# Audio.net
KiCad netlist of a schematic drawn in Altium Designer
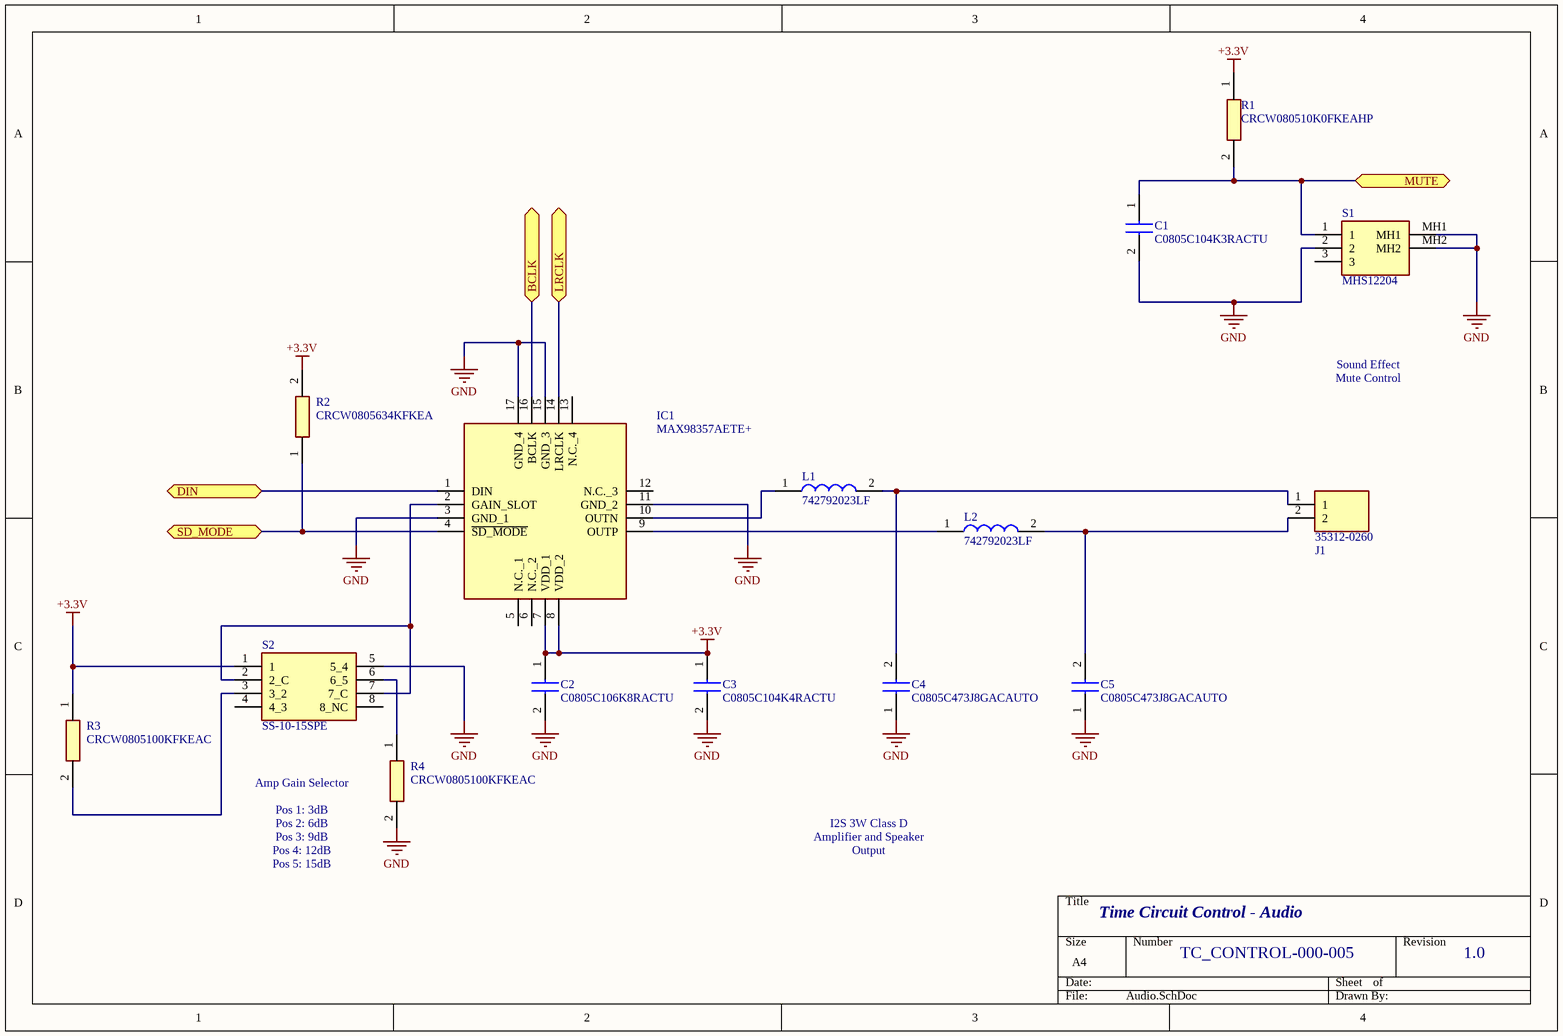
[diagram p0: Audio.SchDoc]

(export (version "E")
  (design (tool "Eeschema 10.0.6"))
  (components
    (comp (ref "C1")
      (value "C0805C104K3RACTU")
      (footprint "SamacSys:CAPC2012X88N")
      (description "Capacitor")
      (fields (field (name "MOUSER PART NUMBER") "80-C0805C104K3R"))
      (libsource (lib "SamacSys") (part "C0805C104K3RACTU"))
    )
    (comp (ref "C2")
      (value "C0805C106K8RACTU")
      (footprint "SamacSys:C0805")
      (description "Capacitor")
      (fields (field (name "MOUSER PART NUMBER") "80-C0805C106K8R"))
      (libsource (lib "SamacSys") (part "C0805C106K8RACTU"))
    )
    (comp (ref "C3")
      (value "C0805C104K4RACTU")
      (footprint "SamacSys:CAPC2012X88N")
      (description "Capacitor")
      (fields (field (name "MOUSER PART NUMBER") "80-C0805C104K4R"))
      (libsource (lib "SamacSys") (part "C0805C104K4RACTU"))
    )
    (comp (ref "C4")
      (value "C0805C473J8GACAUTO")
      (footprint "SamacSys:C0805")
      (description "Capacitor")
      (fields (field (name "MOUSER PART NUMBER") "80-C0805C473J8GAUTO"))
      (libsource (lib "SamacSys") (part "C0805C473J8GACAUTO"))
    )
    (comp (ref "C5")
      (value "C0805C473J8GACAUTO")
      (footprint "SamacSys:C0805")
      (description "Capacitor")
      (fields (field (name "MOUSER PART NUMBER") "80-C0805C473J8GAUTO"))
      (libsource (lib "SamacSys") (part "C0805C473J8GACAUTO"))
    )
    (comp (ref "IC1")
      (value "MAX98357AETE+")
      (footprint "SamacSys:QFN50P300X300X80-17N")
      (description "Integrated Circuit")
      (fields (field (name "MOUSER PART NUMBER") "700-MAX98357AETE+"))
      (libsource (lib "SamacSys") (part "MAX98357AETE+"))
    )
    (comp (ref "J1")
      (value "35312-0260")
      (footprint "SamacSys:SHDR2W64P0X250_1X2_746X650X700P")
      (description "Connector")
      (fields (field (name "MOUSER PART NUMBER") "538-35312-0260"))
      (libsource (lib "SamacSys") (part "35312-0260"))
    )
    (comp (ref "L1")
      (value "742792023LF")
      (footprint "SamacSys:CAPC2012X110N")
      (description "Inductor")
      (libsource (lib "SamacSys") (part "742792023LF"))
    )
    (comp (ref "L2")
      (value "742792023LF")
      (footprint "SamacSys:CAPC2012X110N")
      (description "Inductor")
      (libsource (lib "SamacSys") (part "742792023LF"))
    )
    (comp (ref "R1")
      (value "CRCW080510K0FKEAHP")
      (footprint "SamacSys:RESC2012X60N")
      (description "Resistor")
      (fields (field (name "MOUSER PART NUMBER") "71-CRCW080510K0FKEAH"))
      (libsource (lib "SamacSys") (part "CRCW080510K0FKEAHP"))
    )
    (comp (ref "R2")
      (value "CRCW0805634KFKEA")
      (footprint "SamacSys:RESC2012X50N")
      (description "Resistor")
      (fields (field (name "MOUSER PART NUMBER") "71-CRCW0805634KFKEA"))
      (libsource (lib "SamacSys") (part "CRCW0805634KFKEA"))
    )
    (comp (ref "R3")
      (value "CRCW0805100KFKEAC")
      (footprint "SamacSys:RESC2012X60N")
      (description "Resistor")
      (fields (field (name "MOUSER PART NUMBER") "71-CRCW0805100KFKEAC"))
      (libsource (lib "SamacSys") (part "CRCW0805100KFKEAC"))
    )
    (comp (ref "R4")
      (value "CRCW0805100KFKEAC")
      (footprint "SamacSys:RESC2012X60N")
      (description "Resistor")
      (fields (field (name "MOUSER PART NUMBER") "71-CRCW0805100KFKEAC"))
      (libsource (lib "SamacSys") (part "CRCW0805100KFKEAC"))
    )
    (comp (ref "S1")
      (value "MHS12204")
      (footprint "SamacSys:MHS12204")
      (description "Switch")
      (fields (field (name "MOUSER PART NUMBER") "506-MHS12204"))
      (libsource (lib "SamacSys") (part "MHS12204"))
    )
    (comp (ref "S2")
      (value "SS-10-15SPE")
      (footprint "SamacSys:SS1015SPE")
      (description "Switch")
      (libsource (lib "SamacSys") (part "SS-10-15SPE"))
    )
  )
  (nets
    (net (code "1") (name "+3.3V") (class "Default")
      (node (ref "C2") (pin "1") (pinfunction "1_1") (pintype "passive"))
      (node (ref "C3") (pin "1") (pinfunction "1_1") (pintype "passive"))
      (node (ref "IC1") (pin "7") (pinfunction "VDD_1_7") (pintype "passive"))
      (node (ref "IC1") (pin "8") (pinfunction "VDD_2_8") (pintype "passive"))
      (node (ref "R1") (pin "1") (pinfunction "1_1") (pintype "passive"))
      (node (ref "R2") (pin "2") (pinfunction "2_2") (pintype "passive"))
      (node (ref "R3") (pin "1") (pinfunction "1_1") (pintype "passive"))
      (node (ref "S2") (pin "1") (pinfunction "1_1") (pintype "passive"))
    )
    (net (code "2") (name "/BCLK") (class "Default")
      (node (ref "IC1") (pin "16") (pinfunction "BCLK_16") (pintype "passive"))
    )
    (net (code "3") (name "/DIN") (class "Default")
      (node (ref "IC1") (pin "1") (pinfunction "DIN_1") (pintype "passive"))
    )
    (net (code "4") (name "/LRCLK") (class "Default")
      (node (ref "IC1") (pin "14") (pinfunction "LRCLK_14") (pintype "passive"))
    )
    (net (code "5") (name "/MUTE") (class "Default")
      (node (ref "C1") (pin "1") (pinfunction "1_1") (pintype "passive"))
      (node (ref "R1") (pin "2") (pinfunction "2_2") (pintype "passive"))
      (node (ref "S1") (pin "1") (pinfunction "1_1") (pintype "passive"))
    )
    (net (code "6") (name "/SD_MODE") (class "Default")
      (node (ref "IC1") (pin "4") (pinfunction "~{SD_MODE}_4") (pintype "passive"))
      (node (ref "R2") (pin "1") (pinfunction "1_1") (pintype "passive"))
    )
    (net (code "7") (name "GND") (class "Default")
      (node (ref "C1") (pin "2") (pinfunction "2_2") (pintype "passive"))
      (node (ref "C2") (pin "2") (pinfunction "2_2") (pintype "passive"))
      (node (ref "C3") (pin "2") (pinfunction "2_2") (pintype "passive"))
      (node (ref "C4") (pin "1") (pinfunction "1_1") (pintype "passive"))
      (node (ref "C5") (pin "1") (pinfunction "1_1") (pintype "passive"))
      (node (ref "IC1") (pin "11") (pinfunction "GND_2_11") (pintype "passive"))
      (node (ref "IC1") (pin "15") (pinfunction "GND_3_15") (pintype "passive"))
      (node (ref "IC1") (pin "17") (pinfunction "GND_4_17") (pintype "passive"))
      (node (ref "IC1") (pin "3") (pinfunction "GND_1_3") (pintype "passive"))
      (node (ref "R4") (pin "2") (pinfunction "2_2") (pintype "passive"))
      (node (ref "S1") (pin "2") (pinfunction "2_2") (pintype "passive"))
      (node (ref "S1") (pin "MH1") (pinfunction "MH1_MH1") (pintype "passive"))
      (node (ref "S1") (pin "MH2") (pinfunction "MH2_MH2") (pintype "passive"))
      (node (ref "S2") (pin "5") (pinfunction "5_4_5") (pintype "passive"))
    )
    (net (code "8") (name "Net-(C4-Pad2)") (class "Default")
      (node (ref "C4") (pin "2") (pinfunction "2_2") (pintype "passive"))
      (node (ref "J1") (pin "1") (pinfunction "1_1") (pintype "passive"))
      (node (ref "L1") (pin "2") (pinfunction "2_2") (pintype "passive"))
    )
    (net (code "9") (name "Net-(C5-Pad2)") (class "Default")
      (node (ref "C5") (pin "2") (pinfunction "2_2") (pintype "passive"))
      (node (ref "J1") (pin "2") (pinfunction "2_2") (pintype "passive"))
      (node (ref "L2") (pin "2") (pinfunction "2_2") (pintype "passive"))
    )
    (net (code "10") (name "Net-(IC1-GAIN_SLOT)") (class "Default")
      (node (ref "IC1") (pin "2") (pinfunction "GAIN_SLOT_2") (pintype "passive"))
      (node (ref "S2") (pin "2") (pinfunction "2_C_2") (pintype "passive"))
      (node (ref "S2") (pin "7") (pinfunction "7_C_7") (pintype "passive"))
    )
    (net (code "11") (name "Net-(IC1-OUTN)") (class "Default")
      (node (ref "IC1") (pin "10") (pinfunction "OUTN_10") (pintype "passive"))
      (node (ref "L1") (pin "1") (pinfunction "1_1") (pintype "passive"))
    )
    (net (code "12") (name "Net-(IC1-OUTP)") (class "Default")
      (node (ref "IC1") (pin "9") (pinfunction "OUTP_9") (pintype "passive"))
      (node (ref "L2") (pin "1") (pinfunction "1_1") (pintype "passive"))
    )
    (net (code "13") (name "Net-(S2-3_2)") (class "Default")
      (node (ref "R3") (pin "2") (pinfunction "2_2") (pintype "passive"))
      (node (ref "S2") (pin "3") (pinfunction "3_2_3") (pintype "passive"))
    )
    (net (code "14") (name "Net-(S2-6_5)") (class "Default")
      (node (ref "R4") (pin "1") (pinfunction "1_1") (pintype "passive"))
      (node (ref "S2") (pin "6") (pinfunction "6_5_6") (pintype "passive"))
    )
    (net (code "15") (name "unconnected-(IC1-N.C._1-Pad5)") (class "Default")
      (node (ref "IC1") (pin "5") (pinfunction "N.C._1_5") (pintype "passive"))
    )
    (net (code "16") (name "unconnected-(IC1-N.C._2-Pad6)") (class "Default")
      (node (ref "IC1") (pin "6") (pinfunction "N.C._2_6") (pintype "passive"))
    )
    (net (code "17") (name "unconnected-(IC1-N.C._3-Pad12)") (class "Default")
      (node (ref "IC1") (pin "12") (pinfunction "N.C._3_12") (pintype "passive"))
    )
    (net (code "18") (name "unconnected-(IC1-N.C._4-Pad13)") (class "Default")
      (node (ref "IC1") (pin "13") (pinfunction "N.C._4_13") (pintype "passive"))
    )
    (net (code "19") (name "unconnected-(S1-Pad3)") (class "Default")
      (node (ref "S1") (pin "3") (pinfunction "3_3") (pintype "passive"))
    )
    (net (code "20") (name "unconnected-(S2-4_3-Pad4)") (class "Default")
      (node (ref "S2") (pin "4") (pinfunction "4_3_4") (pintype "passive"))
    )
    (net (code "21") (name "unconnected-(S2-8_NC-Pad8)") (class "Default")
      (node (ref "S2") (pin "8") (pinfunction "8_NC_8") (pintype "passive"))
    )
  )
)
